# Raspi-TPUART.net
KiCad netlist of a schematic drawn in EAGLE
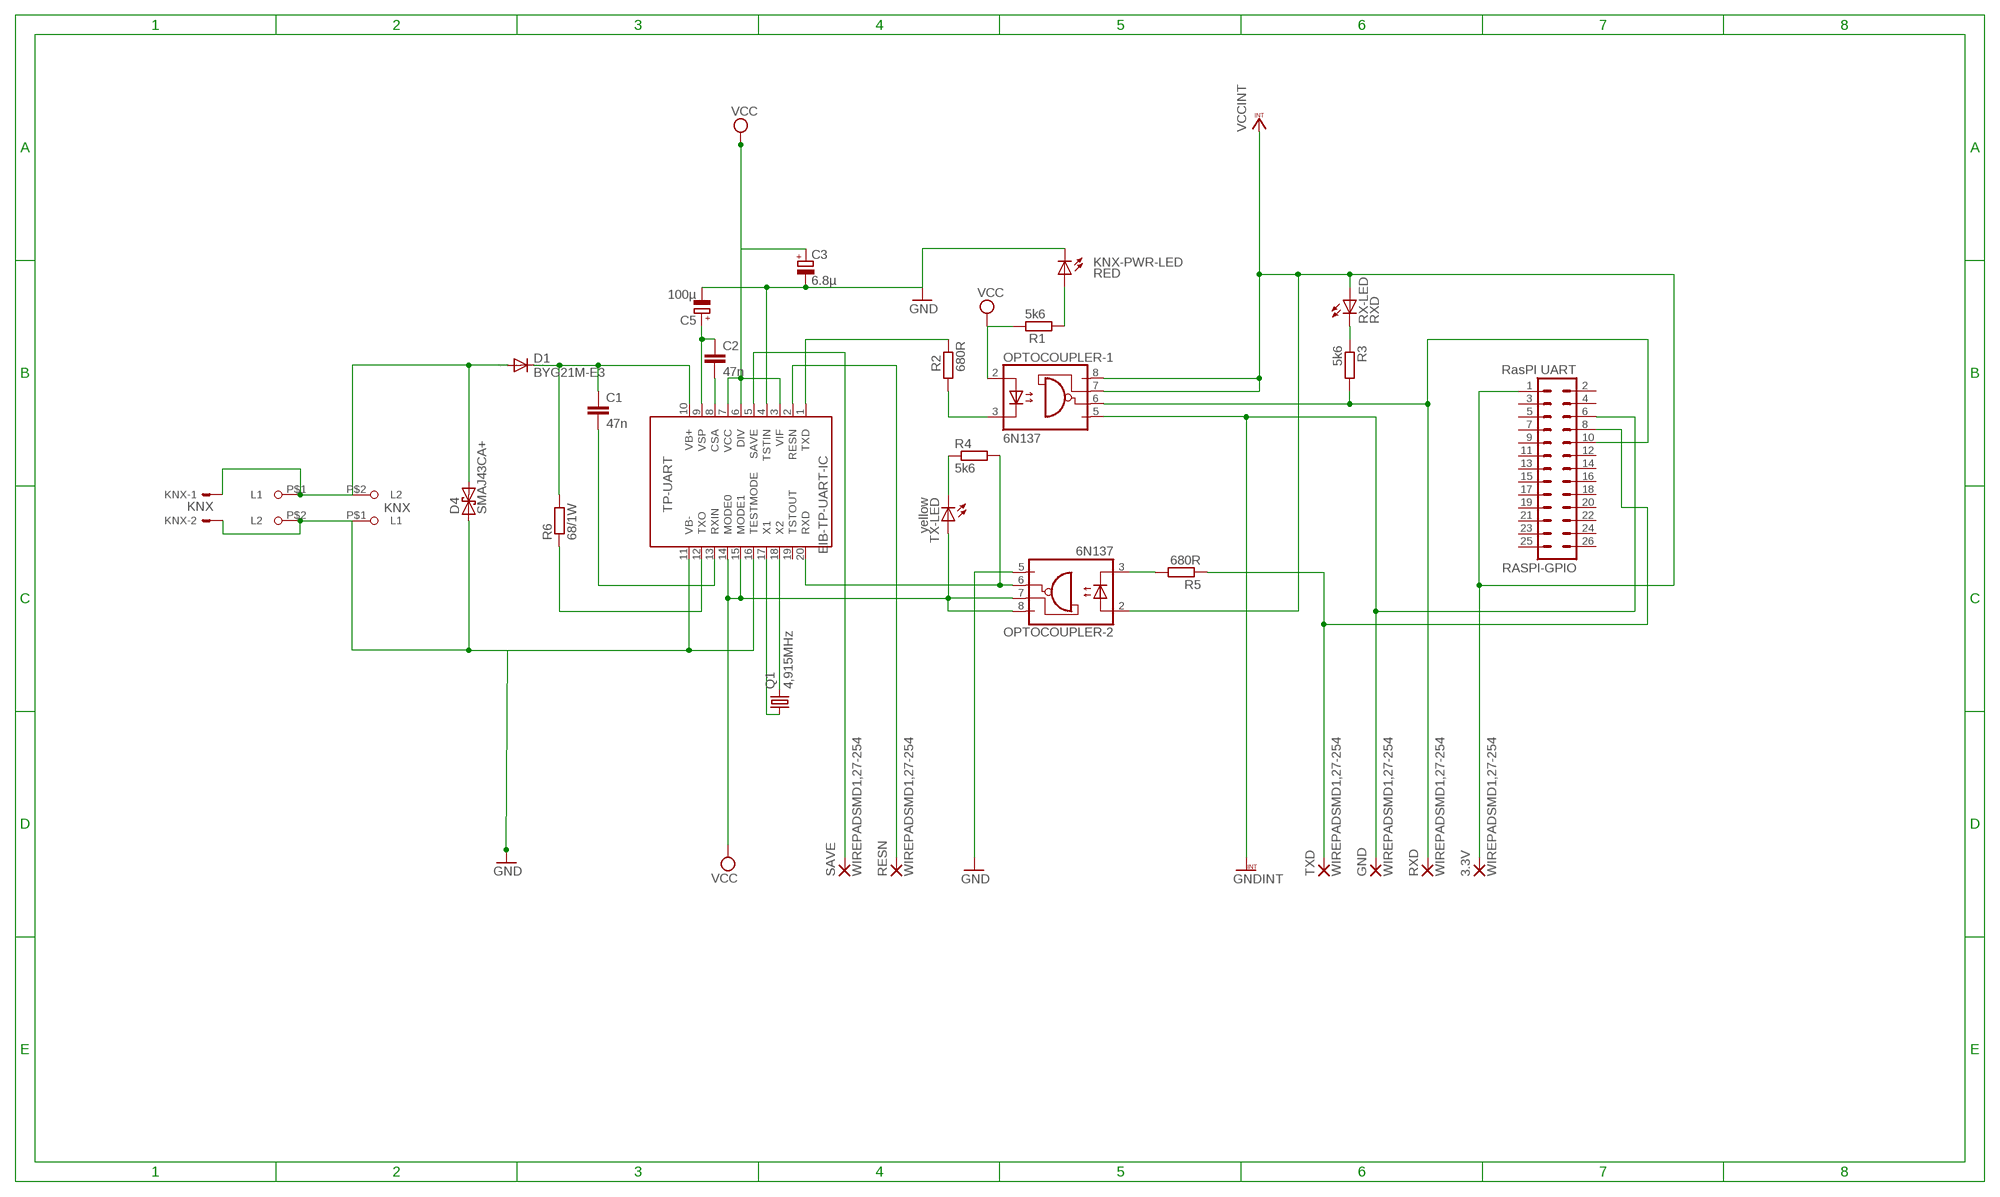
[diagram p0: schematic, sheet 1]

(export (version "E")
  (design (tool "Eeschema 10.0.6"))
  (components
    (comp (ref "3.3V")
      (value "WIREPADSMD1,27-254")
      (footprint "eagle-import:SMD1,27-2,54")
      (libsource (lib "eagle-import") (part "WIREPADSMD1,27-254"))
    )
    (comp (ref "C1")
      (value "47n")
      (footprint "eagle-import:C1206")
      (libsource (lib "eagle-import") (part "C-EUC1206"))
    )
    (comp (ref "C2")
      (value "47n")
      (footprint "eagle-import:C1206")
      (libsource (lib "eagle-import") (part "C-EUC1206"))
    )
    (comp (ref "C3")
      (value "6.8µ")
      (footprint "eagle-import:D_7343-31R")
      (libsource (lib "eagle-import") (part "CPOL-EUD/7343-31R"))
    )
    (comp (ref "C5")
      (value "100µ")
      (footprint "eagle-import:D_7343-31R")
      (libsource (lib "eagle-import") (part "CPOL-EUD/7343-31R"))
    )
    (comp (ref "D1")
      (value "BYG21M-E3")
      (footprint "eagle-import:SMB")
      (libsource (lib "eagle-import") (part "ES2D"))
    )
    (comp (ref "D4")
      (value "SMAJ43CA+")
      (footprint "eagle-import:DO214AA")
      (libsource (lib "eagle-import") (part "BZW04XXB"))
    )
    (comp (ref "EIB-TP-UART-IC")
      (value "TP-UART")
      (footprint "eagle-import:SOIC20")
      (libsource (lib "eagle-import") (part "TP-UART"))
    )
    (comp (ref "GND")
      (value "WIREPADSMD1,27-254")
      (footprint "eagle-import:SMD1,27-2,54")
      (libsource (lib "eagle-import") (part "WIREPADSMD1,27-254"))
    )
    (comp (ref "KNX")
      (value "KNX")
      (footprint "eagle-import:22-23-2021")
      (fields (field (name "MF") "MOLEX") (field (name "MPN") "22-23-2021"))
      (libsource (lib "eagle-import") (part "22-23-2021"))
    )
    (comp (ref "KNX-PWR-LED")
      (value "RED")
      (footprint "eagle-import:KA-3528ASYC")
      (libsource (lib "eagle-import") (part "LEDKA-3528ASYC"))
    )
    (comp (ref "KNX_WAGO_243")
      (value "243-211")
      (footprint "eagle-import:243-211")
      (libsource (lib "eagle-import") (part "243-211"))
    )
    (comp (ref "OPTOCOUPLER-1")
      (value "6N137")
      (footprint "eagle-import:DIL8-SMD")
      (libsource (lib "eagle-import") (part "6N137"))
    )
    (comp (ref "OPTOCOUPLER-2")
      (value "6N137")
      (footprint "eagle-import:DIL8-SMD")
      (libsource (lib "eagle-import") (part "6N137"))
    )
    (comp (ref "Q1")
      (value "4,915MHz")
      (footprint "eagle-import:HC49UP")
      (libsource (lib "eagle-import") (part "CRYSTALHC49UP"))
    )
    (comp (ref "R1")
      (value "5k6")
      (footprint "eagle-import:M1206")
      (libsource (lib "eagle-import") (part "R-EU_M1206"))
    )
    (comp (ref "R2")
      (value "680R")
      (footprint "eagle-import:M1206")
      (libsource (lib "eagle-import") (part "R-EU_M1206"))
    )
    (comp (ref "R3")
      (value "5k6")
      (footprint "eagle-import:M1206")
      (libsource (lib "eagle-import") (part "R-EU_M1206"))
    )
    (comp (ref "R4")
      (value "5k6")
      (footprint "eagle-import:M1206")
      (libsource (lib "eagle-import") (part "R-EU_M1206"))
    )
    (comp (ref "R5")
      (value "680R")
      (footprint "eagle-import:M1206")
      (libsource (lib "eagle-import") (part "R-EU_M1206"))
    )
    (comp (ref "R6")
      (value "68/1W")
      (footprint "eagle-import:R2512")
      (libsource (lib "eagle-import") (part "R-EU_R2512"))
    )
    (comp (ref "RASPI-GPIO")
      (value "RasPI UART")
      (footprint "eagle-import:MA13-2")
      (libsource (lib "eagle-import") (part "MA13-2"))
    )
    (comp (ref "RESN")
      (value "WIREPADSMD1,27-254")
      (footprint "eagle-import:SMD1,27-2,54")
      (libsource (lib "eagle-import") (part "WIREPADSMD1,27-254"))
    )
    (comp (ref "RX-LED")
      (value "RXD")
      (footprint "eagle-import:KA-3528ASYC")
      (libsource (lib "eagle-import") (part "LEDKA-3528ASYC"))
    )
    (comp (ref "RXD")
      (value "WIREPADSMD1,27-254")
      (footprint "eagle-import:SMD1,27-2,54")
      (libsource (lib "eagle-import") (part "WIREPADSMD1,27-254"))
    )
    (comp (ref "SAVE")
      (value "WIREPADSMD1,27-254")
      (footprint "eagle-import:SMD1,27-2,54")
      (libsource (lib "eagle-import") (part "WIREPADSMD1,27-254"))
    )
    (comp (ref "TX-LED")
      (value "yellow")
      (footprint "eagle-import:KA-3528ASYC")
      (libsource (lib "eagle-import") (part "LEDKA-3528ASYC"))
    )
    (comp (ref "TXD")
      (value "WIREPADSMD1,27-254")
      (footprint "eagle-import:SMD1,27-2,54")
      (libsource (lib "eagle-import") (part "WIREPADSMD1,27-254"))
    )
    (comp (ref "U$1")
      (value "243-211")
      (footprint "eagle-import:243-211")
      (libsource (lib "eagle-import") (part "243-211"))
    )
  )
  (nets
    (net (code "1") (name "GND") (class "Default")
      (node (ref "C3") (pin "-") (pinfunction "-_-") (pintype "passive"))
      (node (ref "C5") (pin "-") (pinfunction "-_-") (pintype "passive"))
      (node (ref "D4") (pin "A") (pinfunction "1_A") (pintype "passive"))
      (node (ref "EIB-TP-UART-IC") (pin "11") (pinfunction "VB-_11") (pintype "passive"))
      (node (ref "EIB-TP-UART-IC") (pin "16") (pinfunction "TESTMODE_16") (pintype "input"))
      (node (ref "EIB-TP-UART-IC") (pin "4") (pinfunction "TSTIN_4") (pintype "bidirectional"))
      (node (ref "KNX") (pin "2") (pinfunction "S_2") (pintype "passive"))
      (node (ref "KNX-PWR-LED") (pin "C") (pinfunction "C_C") (pintype "passive"))
      (node (ref "KNX_WAGO_243") (pin "P$1") (pinfunction "L1_P$1") (pintype "bidirectional"))
      (node (ref "OPTOCOUPLER-2") (pin "5") (pinfunction "GND_5") (pintype "passive"))
      (node (ref "U$1") (pin "P$2") (pinfunction "L2_P$2") (pintype "bidirectional"))
    )
    (net (code "2") (name "GNDINT") (class "Default")
      (node (ref "GND") (pin "1") (pinfunction "P_1") (pintype "passive"))
      (node (ref "OPTOCOUPLER-1") (pin "5") (pinfunction "GND_5") (pintype "passive"))
      (node (ref "RASPI-GPIO") (pin "6") (pinfunction "6_6") (pintype "passive"))
    )
    (net (code "3") (name "Net-(D4-2)") (class "Default")
      (node (ref "D1") (pin "A") (pinfunction "A_A") (pintype "passive"))
      (node (ref "D4") (pin "C") (pinfunction "2_C") (pintype "passive"))
      (node (ref "KNX") (pin "1") (pinfunction "S_1") (pintype "passive"))
      (node (ref "KNX_WAGO_243") (pin "P$2") (pinfunction "L2_P$2") (pintype "bidirectional"))
      (node (ref "U$1") (pin "P$1") (pinfunction "L1_P$1") (pintype "bidirectional"))
    )
    (net (code "4") (name "Net-(EIB-TP-UART-IC-CSA)") (class "Default")
      (node (ref "C2") (pin "2") (pinfunction "2_2") (pintype "passive"))
      (node (ref "EIB-TP-UART-IC") (pin "8") (pinfunction "CSA_8") (pintype "passive"))
    )
    (net (code "5") (name "Net-(EIB-TP-UART-IC-RESN)") (class "Default")
      (node (ref "EIB-TP-UART-IC") (pin "2") (pinfunction "RESN_2") (pintype "bidirectional"))
      (node (ref "RESN") (pin "1") (pinfunction "P_1") (pintype "passive"))
    )
    (net (code "6") (name "Net-(EIB-TP-UART-IC-RXD)") (class "Default")
      (node (ref "EIB-TP-UART-IC") (pin "20") (pinfunction "RXD_20") (pintype "input"))
      (node (ref "OPTOCOUPLER-2") (pin "6") (pinfunction "VO_6") (pintype "passive"))
      (node (ref "R4") (pin "2") (pinfunction "2_2") (pintype "passive"))
    )
    (net (code "7") (name "Net-(EIB-TP-UART-IC-RXIN)") (class "Default")
      (node (ref "C1") (pin "2") (pinfunction "2_2") (pintype "passive"))
      (node (ref "EIB-TP-UART-IC") (pin "13") (pinfunction "RXIN_13") (pintype "input"))
    )
    (net (code "8") (name "Net-(EIB-TP-UART-IC-SAVE)") (class "Default")
      (node (ref "EIB-TP-UART-IC") (pin "5") (pinfunction "SAVE_5") (pintype "open_collector"))
      (node (ref "SAVE") (pin "1") (pinfunction "P_1") (pintype "passive"))
    )
    (net (code "9") (name "Net-(EIB-TP-UART-IC-TXD)") (class "Default")
      (node (ref "EIB-TP-UART-IC") (pin "1") (pinfunction "TXD_1") (pintype "output"))
      (node (ref "R2") (pin "2") (pinfunction "2_2") (pintype "passive"))
    )
    (net (code "10") (name "Net-(EIB-TP-UART-IC-TXO)") (class "Default")
      (node (ref "EIB-TP-UART-IC") (pin "12") (pinfunction "TXO_12") (pintype "output"))
      (node (ref "R6") (pin "1") (pinfunction "1_1") (pintype "passive"))
    )
    (net (code "11") (name "Net-(EIB-TP-UART-IC-VB+)") (class "Default")
      (node (ref "C1") (pin "1") (pinfunction "1_1") (pintype "passive"))
      (node (ref "D1") (pin "C") (pinfunction "C_C") (pintype "passive"))
      (node (ref "EIB-TP-UART-IC") (pin "10") (pinfunction "VB+_10") (pintype "passive"))
      (node (ref "R6") (pin "2") (pinfunction "2_2") (pintype "passive"))
    )
    (net (code "12") (name "Net-(EIB-TP-UART-IC-VSP)") (class "Default")
      (node (ref "C2") (pin "1") (pinfunction "1_1") (pintype "passive"))
      (node (ref "C5") (pin "+") (pinfunction "+_+") (pintype "passive"))
      (node (ref "EIB-TP-UART-IC") (pin "9") (pinfunction "VSP_9") (pintype "passive"))
    )
    (net (code "13") (name "Net-(EIB-TP-UART-IC-X1)") (class "Default")
      (node (ref "EIB-TP-UART-IC") (pin "17") (pinfunction "X1_17") (pintype "passive"))
      (node (ref "Q1") (pin "1") (pinfunction "1_1") (pintype "passive"))
    )
    (net (code "14") (name "Net-(EIB-TP-UART-IC-X2)") (class "Default")
      (node (ref "EIB-TP-UART-IC") (pin "18") (pinfunction "X2_18") (pintype "passive"))
      (node (ref "Q1") (pin "2") (pinfunction "2_2") (pintype "passive"))
    )
    (net (code "15") (name "Net-(KNX-PWR-LED-PadA)") (class "Default")
      (node (ref "KNX-PWR-LED") (pin "A") (pinfunction "A_A") (pintype "passive"))
      (node (ref "R1") (pin "1") (pinfunction "1_1") (pintype "passive"))
    )
    (net (code "16") (name "Net-(OPTOCOUPLER-1-C)") (class "Default")
      (node (ref "OPTOCOUPLER-1") (pin "3") (pinfunction "C_3") (pintype "passive"))
      (node (ref "R2") (pin "1") (pinfunction "1_1") (pintype "passive"))
    )
    (net (code "17") (name "Net-(OPTOCOUPLER-1-VO)") (class "Default")
      (node (ref "OPTOCOUPLER-1") (pin "6") (pinfunction "VO_6") (pintype "passive"))
      (node (ref "R3") (pin "2") (pinfunction "2_2") (pintype "passive"))
      (node (ref "RASPI-GPIO") (pin "10") (pinfunction "10_10") (pintype "passive"))
      (node (ref "RXD") (pin "1") (pinfunction "P_1") (pintype "passive"))
    )
    (net (code "18") (name "Net-(OPTOCOUPLER-2-C)") (class "Default")
      (node (ref "OPTOCOUPLER-2") (pin "3") (pinfunction "C_3") (pintype "passive"))
      (node (ref "R5") (pin "2") (pinfunction "2_2") (pintype "passive"))
    )
    (net (code "19") (name "Net-(R3-Pad1)") (class "Default")
      (node (ref "R3") (pin "1") (pinfunction "1_1") (pintype "passive"))
      (node (ref "RX-LED") (pin "C") (pinfunction "C_C") (pintype "passive"))
    )
    (net (code "20") (name "Net-(R4-Pad1)") (class "Default")
      (node (ref "R4") (pin "1") (pinfunction "1_1") (pintype "passive"))
      (node (ref "TX-LED") (pin "C") (pinfunction "C_C") (pintype "passive"))
    )
    (net (code "21") (name "Net-(TXD-P)") (class "Default")
      (node (ref "R5") (pin "1") (pinfunction "1_1") (pintype "passive"))
      (node (ref "RASPI-GPIO") (pin "8") (pinfunction "8_8") (pintype "passive"))
      (node (ref "TXD") (pin "1") (pinfunction "P_1") (pintype "passive"))
    )
    (net (code "22") (name "VCC") (class "Default")
      (node (ref "C3") (pin "+") (pinfunction "+_+") (pintype "passive"))
      (node (ref "EIB-TP-UART-IC") (pin "14") (pinfunction "MODE0_14") (pintype "input"))
      (node (ref "EIB-TP-UART-IC") (pin "15") (pinfunction "MODE1_15") (pintype "input"))
      (node (ref "EIB-TP-UART-IC") (pin "3") (pinfunction "VIF_3") (pintype "input"))
      (node (ref "EIB-TP-UART-IC") (pin "6") (pinfunction "DIV_6") (pintype "input"))
      (node (ref "EIB-TP-UART-IC") (pin "7") (pinfunction "VCC_7") (pintype "output"))
      (node (ref "OPTOCOUPLER-1") (pin "2") (pinfunction "A_2") (pintype "passive"))
      (node (ref "OPTOCOUPLER-2") (pin "7") (pinfunction "VE_7") (pintype "passive"))
      (node (ref "OPTOCOUPLER-2") (pin "8") (pinfunction "VCC_8") (pintype "passive"))
      (node (ref "R1") (pin "2") (pinfunction "2_2") (pintype "passive"))
      (node (ref "TX-LED") (pin "A") (pinfunction "A_A") (pintype "passive"))
    )
    (net (code "23") (name "VCCINT") (class "Default")
      (node (ref "3.3V") (pin "1") (pinfunction "P_1") (pintype "passive"))
      (node (ref "OPTOCOUPLER-1") (pin "7") (pinfunction "VE_7") (pintype "passive"))
      (node (ref "OPTOCOUPLER-1") (pin "8") (pinfunction "VCC_8") (pintype "passive"))
      (node (ref "OPTOCOUPLER-2") (pin "2") (pinfunction "A_2") (pintype "passive"))
      (node (ref "RASPI-GPIO") (pin "1") (pinfunction "1_1") (pintype "passive"))
      (node (ref "RX-LED") (pin "A") (pinfunction "A_A") (pintype "passive"))
    )
    (net (code "24") (name "unconnected-(EIB-TP-UART-IC-TSTOUT-Pad19)") (class "Default")
      (node (ref "EIB-TP-UART-IC") (pin "19") (pinfunction "TSTOUT_19") (pintype "output"))
    )
    (net (code "25") (name "unconnected-(RASPI-GPIO-Pad2)") (class "Default")
      (node (ref "RASPI-GPIO") (pin "2") (pinfunction "2_2") (pintype "passive"))
    )
    (net (code "26") (name "unconnected-(RASPI-GPIO-Pad3)") (class "Default")
      (node (ref "RASPI-GPIO") (pin "3") (pinfunction "3_3") (pintype "passive"))
    )
    (net (code "27") (name "unconnected-(RASPI-GPIO-Pad4)") (class "Default")
      (node (ref "RASPI-GPIO") (pin "4") (pinfunction "4_4") (pintype "passive"))
    )
    (net (code "28") (name "unconnected-(RASPI-GPIO-Pad5)") (class "Default")
      (node (ref "RASPI-GPIO") (pin "5") (pinfunction "5_5") (pintype "passive"))
    )
    (net (code "29") (name "unconnected-(RASPI-GPIO-Pad7)") (class "Default")
      (node (ref "RASPI-GPIO") (pin "7") (pinfunction "7_7") (pintype "passive"))
    )
    (net (code "30") (name "unconnected-(RASPI-GPIO-Pad9)") (class "Default")
      (node (ref "RASPI-GPIO") (pin "9") (pinfunction "9_9") (pintype "passive"))
    )
    (net (code "31") (name "unconnected-(RASPI-GPIO-Pad11)") (class "Default")
      (node (ref "RASPI-GPIO") (pin "11") (pinfunction "11_11") (pintype "passive"))
    )
    (net (code "32") (name "unconnected-(RASPI-GPIO-Pad12)") (class "Default")
      (node (ref "RASPI-GPIO") (pin "12") (pinfunction "12_12") (pintype "passive"))
    )
    (net (code "33") (name "unconnected-(RASPI-GPIO-Pad13)") (class "Default")
      (node (ref "RASPI-GPIO") (pin "13") (pinfunction "13_13") (pintype "passive"))
    )
    (net (code "34") (name "unconnected-(RASPI-GPIO-Pad14)") (class "Default")
      (node (ref "RASPI-GPIO") (pin "14") (pinfunction "14_14") (pintype "passive"))
    )
    (net (code "35") (name "unconnected-(RASPI-GPIO-Pad15)") (class "Default")
      (node (ref "RASPI-GPIO") (pin "15") (pinfunction "15_15") (pintype "passive"))
    )
    (net (code "36") (name "unconnected-(RASPI-GPIO-Pad16)") (class "Default")
      (node (ref "RASPI-GPIO") (pin "16") (pinfunction "16_16") (pintype "passive"))
    )
    (net (code "37") (name "unconnected-(RASPI-GPIO-Pad17)") (class "Default")
      (node (ref "RASPI-GPIO") (pin "17") (pinfunction "17_17") (pintype "passive"))
    )
    (net (code "38") (name "unconnected-(RASPI-GPIO-Pad18)") (class "Default")
      (node (ref "RASPI-GPIO") (pin "18") (pinfunction "18_18") (pintype "passive"))
    )
    (net (code "39") (name "unconnected-(RASPI-GPIO-Pad19)") (class "Default")
      (node (ref "RASPI-GPIO") (pin "19") (pinfunction "19_19") (pintype "passive"))
    )
    (net (code "40") (name "unconnected-(RASPI-GPIO-Pad20)") (class "Default")
      (node (ref "RASPI-GPIO") (pin "20") (pinfunction "20_20") (pintype "passive"))
    )
    (net (code "41") (name "unconnected-(RASPI-GPIO-Pad21)") (class "Default")
      (node (ref "RASPI-GPIO") (pin "21") (pinfunction "21_21") (pintype "passive"))
    )
    (net (code "42") (name "unconnected-(RASPI-GPIO-Pad22)") (class "Default")
      (node (ref "RASPI-GPIO") (pin "22") (pinfunction "22_22") (pintype "passive"))
    )
    (net (code "43") (name "unconnected-(RASPI-GPIO-Pad23)") (class "Default")
      (node (ref "RASPI-GPIO") (pin "23") (pinfunction "23_23") (pintype "passive"))
    )
    (net (code "44") (name "unconnected-(RASPI-GPIO-Pad24)") (class "Default")
      (node (ref "RASPI-GPIO") (pin "24") (pinfunction "24_24") (pintype "passive"))
    )
    (net (code "45") (name "unconnected-(RASPI-GPIO-Pad25)") (class "Default")
      (node (ref "RASPI-GPIO") (pin "25") (pinfunction "25_25") (pintype "passive"))
    )
    (net (code "46") (name "unconnected-(RASPI-GPIO-Pad26)") (class "Default")
      (node (ref "RASPI-GPIO") (pin "26") (pinfunction "26_26") (pintype "passive"))
    )
  )
)
